# MCU.net
KiCad netlist of a schematic drawn in Altium Designer
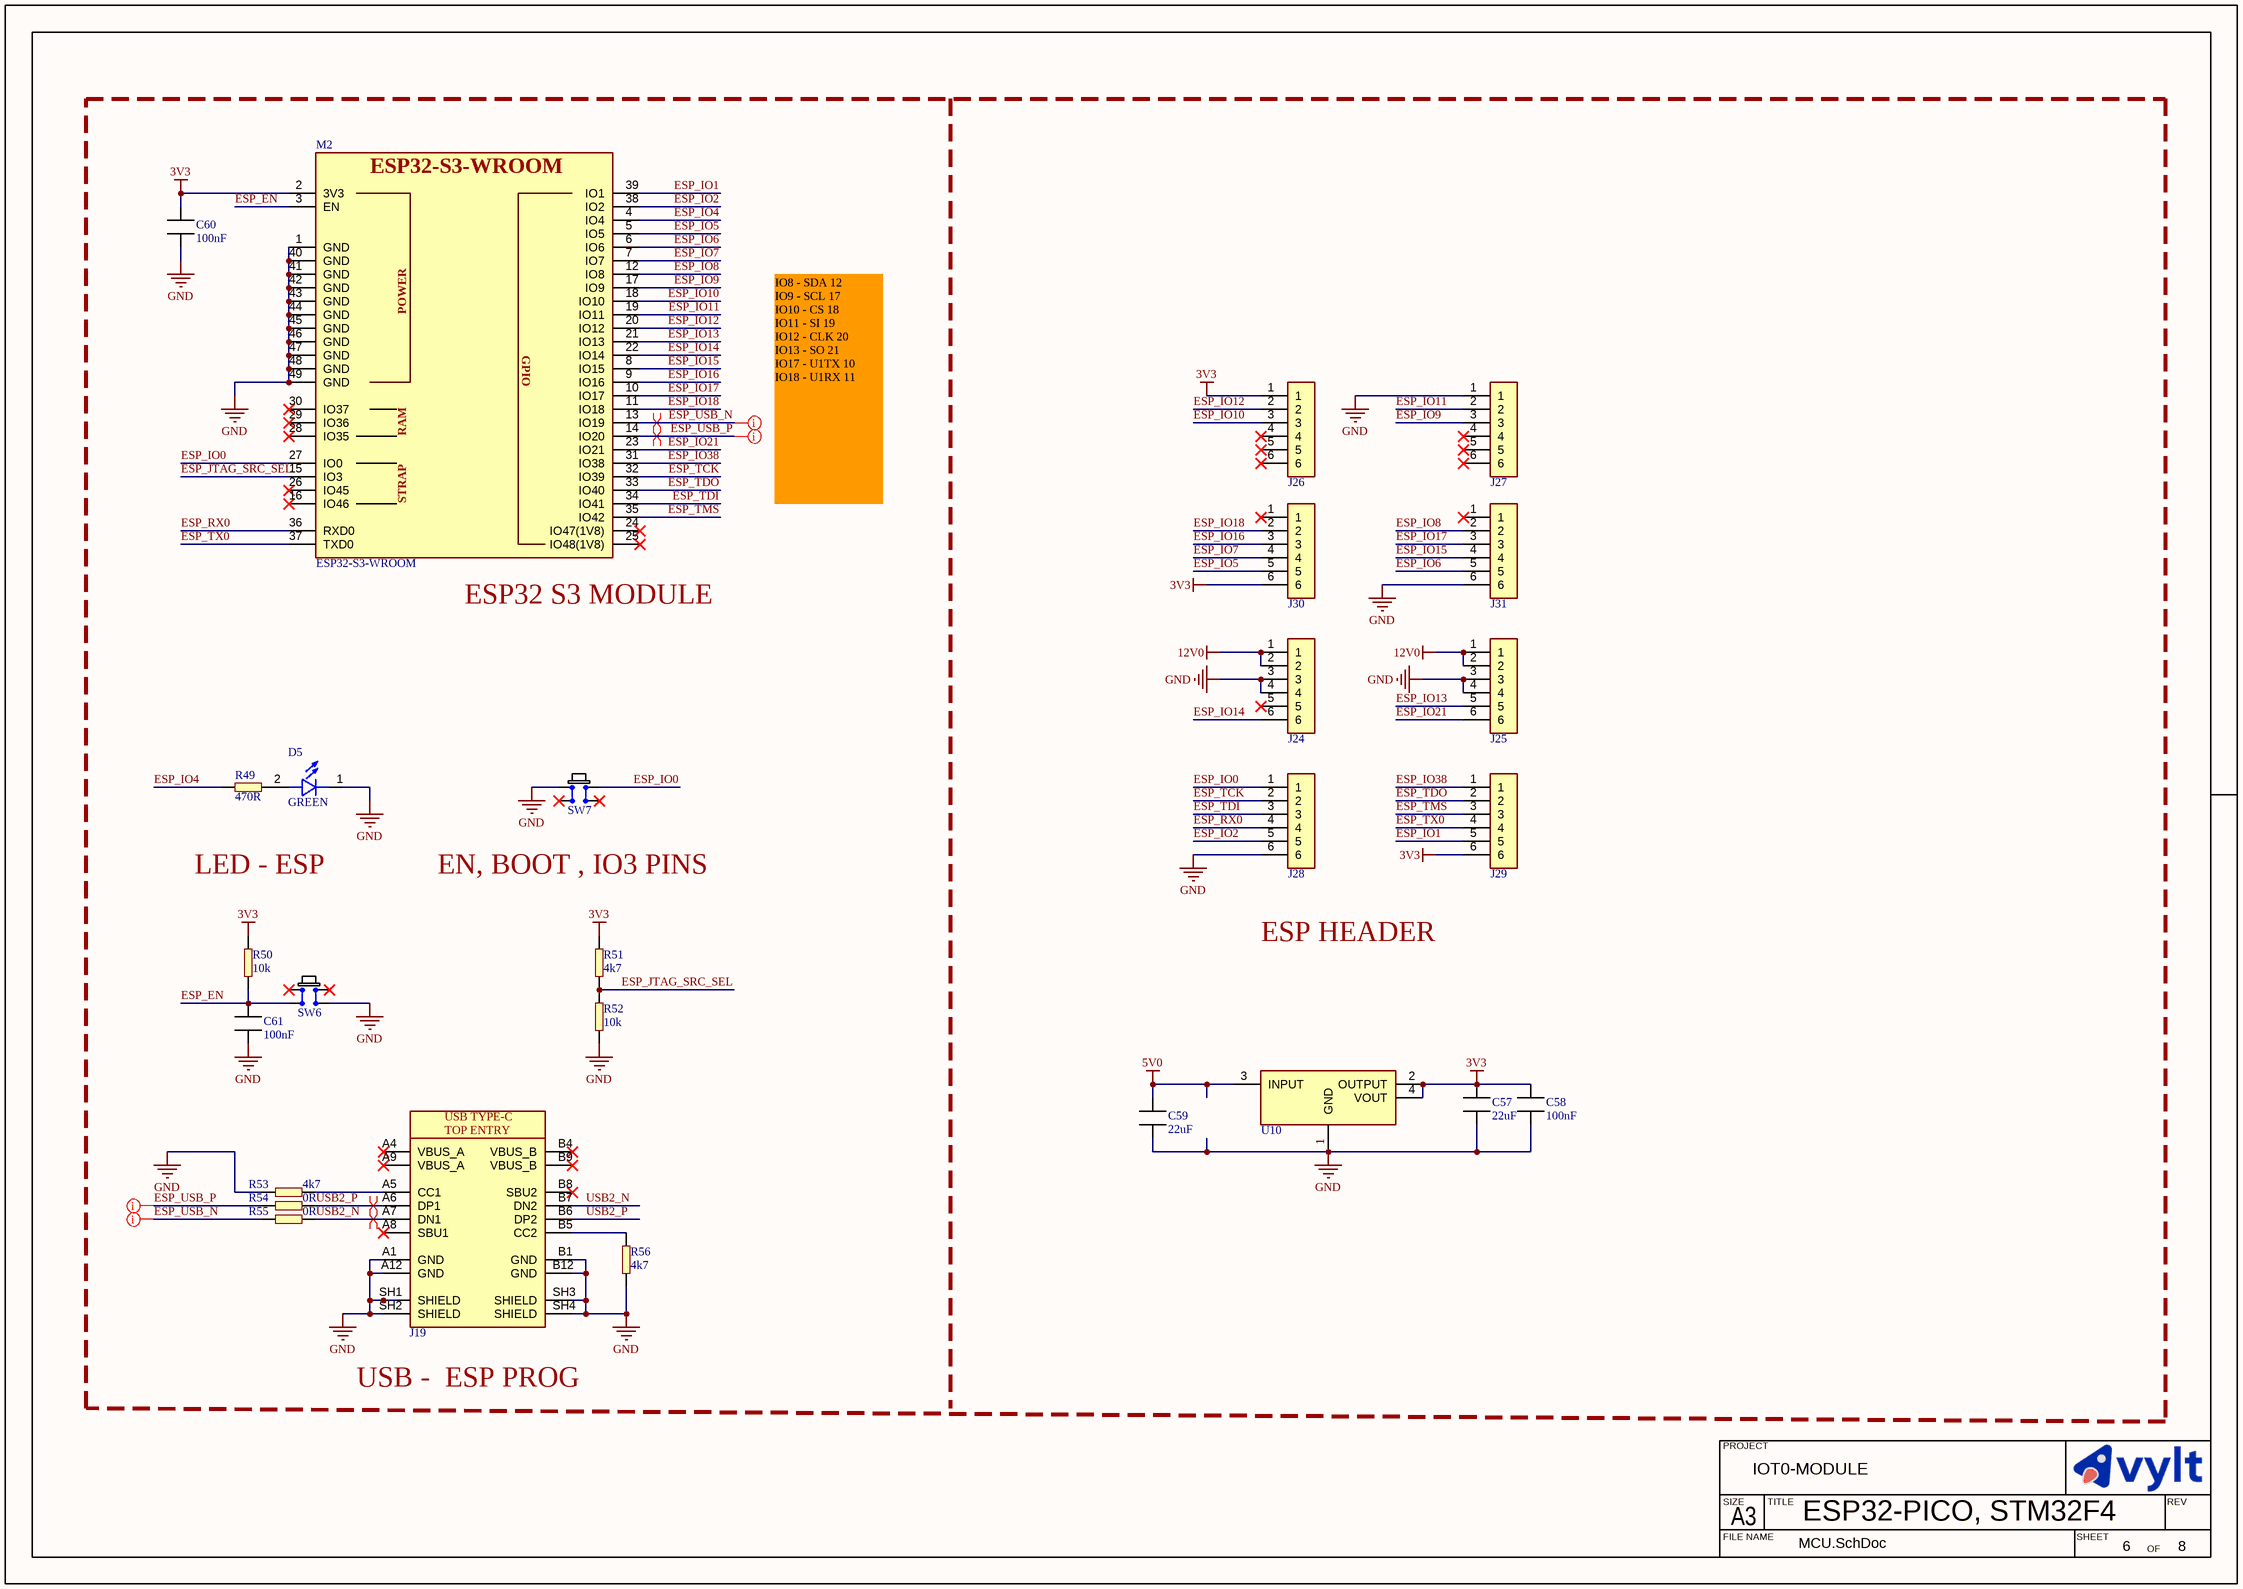
[diagram p0: MCU.SchDoc]

(export (version "E")
  (design (tool "Eeschema 10.0.6"))
  (components
    (comp (ref "C57")
      (value "22uF")
      (footprint "CAPC2012X13L")
      (description "Chip Capacitor, 2-Leads, Body 2.00x1.25mm, IPC High Density")
      (fields (field (name "Comment") "MLCC_0805"))
      (libsource (lib "Capacitor") (part "MLCC_0805"))
    )
    (comp (ref "C58")
      (value "100nF")
      (footprint "CAPC2012X13L")
      (description "Chip Capacitor, 2-Leads, Body 2.00x1.25mm, IPC High Density")
      (fields (field (name "Comment") "MLCC_0805"))
      (libsource (lib "Capacitor") (part "MLCC_0805"))
    )
    (comp (ref "C59")
      (value "22uF")
      (footprint "CAPC2012X13L")
      (description "Chip Capacitor, 2-Leads, Body 2.00x1.25mm, IPC High Density")
      (fields (field (name "Comment") "MLCC_0805"))
      (libsource (lib "Capacitor") (part "MLCC_0805"))
    )
    (comp (ref "C60")
      (value "100nF")
      (footprint "CAPC2012X13L")
      (description "Chip Capacitor, 2-Leads, Body 2.00x1.25mm, IPC High Density")
      (fields (field (name "Comment") "MLCC_0805"))
      (libsource (lib "Capacitor") (part "MLCC_0805"))
    )
    (comp (ref "C61")
      (value "100nF")
      (footprint "CAPC2012X13L")
      (description "Chip Capacitor, 2-Leads, Body 2.00x1.25mm, IPC High Density")
      (fields (field (name "Comment") "MLCC_0805"))
      (libsource (lib "Capacitor") (part "MLCC_0805"))
    )
    (comp (ref "D5")
      (value "GREEN")
      (footprint "LED_1206")
      (description "LED CLEAR 1206 SMD")
      (fields (field (name "Comment") "LED_1206"))
      (libsource (lib "LED") (part "LED_1206"))
    )
    (comp (ref "J19")
      (value "GSB1CA11101DSHR")
      (footprint "GSB1CA11101DSHR")
      (libsource (lib "Connectors") (part "GSB1CA11101DSHR"))
    )
    (comp (ref "J24")
      (value "ERP_148-2")
      (footprint "6PX1R_F")
      (description "6PX1R Female Header")
      (libsource (lib "PinHeader") (part "6PX1R_F"))
    )
    (comp (ref "J25")
      (value "ERP_148-2")
      (footprint "6PX1R_F")
      (description "6PX1R Female Header")
      (libsource (lib "PinHeader") (part "6PX1R_F"))
    )
    (comp (ref "J26")
      (value "ERP_148-2")
      (footprint "6PX1R_F")
      (description "6PX1R Female Header")
      (libsource (lib "PinHeader") (part "6PX1R_F"))
    )
    (comp (ref "J27")
      (value "ERP_148-2")
      (footprint "6PX1R_F")
      (description "6PX1R Female Header")
      (libsource (lib "PinHeader") (part "6PX1R_F"))
    )
    (comp (ref "J28")
      (value "ERP_148-2")
      (footprint "6PX1R_F")
      (description "6PX1R Female Header")
      (libsource (lib "PinHeader") (part "6PX1R_F"))
    )
    (comp (ref "J29")
      (value "ERP_148-2")
      (footprint "6PX1R_F")
      (description "6PX1R Female Header")
      (libsource (lib "PinHeader") (part "6PX1R_F"))
    )
    (comp (ref "J30")
      (value "ERP_148-2")
      (footprint "6PX1R_F")
      (description "6PX1R Female Header")
      (libsource (lib "PinHeader") (part "6PX1R_F"))
    )
    (comp (ref "J31")
      (value "ERP_148-2")
      (footprint "6PX1R_F")
      (description "6PX1R Female Header")
      (libsource (lib "PinHeader") (part "6PX1R_F"))
    )
    (comp (ref "M2")
      (value "ESP32-S3-WROOM")
      (footprint "ESP32-S3-WROOM-1")
      (description "ESP32-S3-WROOM 1/1U Module")
      (fields (field (name "Comment") "ESP32-S3-WROOM-1(U)"))
      (libsource (lib "ESP") (part "ESP32-S3-WROOM-1(U)"))
    )
    (comp (ref "R49")
      (value "470R")
      (footprint "RES_0603")
      (description "RES_0603")
      (fields (field (name "Comment") "ERP_101-1"))
      (libsource (lib "Resistor") (part "RES_0603"))
    )
    (comp (ref "R50")
      (value "10k")
      (footprint "RES_0603")
      (description "RES_0603")
      (fields (field (name "Comment") "ERP_101-1"))
      (libsource (lib "") (part "RES_0603_1"))
    )
    (comp (ref "R51")
      (value "4k7")
      (footprint "RES_0603")
      (description "RES_0603")
      (fields (field (name "Comment") "ERP_101-1"))
      (libsource (lib "") (part "RES_0603_1"))
    )
    (comp (ref "R52")
      (value "10k")
      (footprint "RES_0603")
      (description "RES_0603")
      (fields (field (name "Comment") "ERP_101-1"))
      (libsource (lib "") (part "RES_0603_1"))
    )
    (comp (ref "R53")
      (value "4k7")
      (footprint "RES_0603")
      (description "RES_0603")
      (fields (field (name "Comment") "ERP_101-1"))
      (libsource (lib "Resistor") (part "RES_0603"))
    )
    (comp (ref "R54")
      (value "0R")
      (footprint "RES_0603")
      (description "RES_0603")
      (fields (field (name "Comment") "ERP_101-1"))
      (libsource (lib "Resistor") (part "RES_0603"))
    )
    (comp (ref "R55")
      (value "0R")
      (footprint "RES_0603")
      (description "RES_0603")
      (fields (field (name "Comment") "ERP_101-1"))
      (libsource (lib "Resistor") (part "RES_0603"))
    )
    (comp (ref "R56")
      (value "4k7")
      (footprint "RES_0603")
      (description "RES_0603")
      (fields (field (name "Comment") "ERP_101-1"))
      (libsource (lib "") (part "RES_0603_2"))
    )
    (comp (ref "SW6")
      (value "Generic6X6")
      (footprint "Generic6X6")
      (description "Tactile Switch SPST-NO Top Actuated Surface Mount")
      (libsource (lib "Switch") (part "Generic6X6"))
    )
    (comp (ref "SW7")
      (value "Generic6X6")
      (footprint "Generic6X6")
      (description "Tactile Switch SPST-NO Top Actuated Surface Mount")
      (libsource (lib "Switch") (part "Generic6X6"))
    )
    (comp (ref "U10")
      (value "ERP_123-1")
      (footprint "AMS1117_SOT223")
      (description "AMS1117 LDO")
      (libsource (lib "VoltageRegulator") (part "AMS1117_SOT223"))
    )
  )
  (nets
    (net (code "1") (name "/ESP_EN") (class "Default")
      (node (ref "C61") (pin "1") (pinfunction "1_1") (pintype "passive"))
      (node (ref "M2") (pin "3") (pinfunction "EN_3") (pintype "passive"))
      (node (ref "R50") (pin "1") (pinfunction "1_1") (pintype "passive"))
      (node (ref "SW6") (pin "2") (pinfunction "NO_2") (pintype "passive"))
    )
    (net (code "2") (name "/ESP_IO0") (class "Default")
      (node (ref "J28") (pin "1") (pinfunction "1_1") (pintype "passive"))
      (node (ref "M2") (pin "27") (pinfunction "IO0_27") (pintype "passive"))
      (node (ref "SW7") (pin "3") (pinfunction "COM_3") (pintype "passive"))
    )
    (net (code "3") (name "/ESP_IO1") (class "Default")
      (node (ref "J29") (pin "5") (pinfunction "5_5") (pintype "passive"))
      (node (ref "M2") (pin "39") (pinfunction "IO1_39") (pintype "passive"))
    )
    (net (code "4") (name "/ESP_IO2") (class "Default")
      (node (ref "J28") (pin "5") (pinfunction "5_5") (pintype "passive"))
      (node (ref "M2") (pin "38") (pinfunction "IO2_38") (pintype "passive"))
    )
    (net (code "5") (name "/ESP_IO4") (class "Default")
      (node (ref "M2") (pin "4") (pinfunction "IO4_4") (pintype "passive"))
      (node (ref "R49") (pin "2") (pinfunction "2_2") (pintype "passive"))
    )
    (net (code "6") (name "/ESP_IO5") (class "Default")
      (node (ref "J30") (pin "5") (pinfunction "5_5") (pintype "passive"))
      (node (ref "M2") (pin "5") (pinfunction "IO5_5") (pintype "passive"))
    )
    (net (code "7") (name "/ESP_IO6") (class "Default")
      (node (ref "J31") (pin "5") (pinfunction "5_5") (pintype "passive"))
      (node (ref "M2") (pin "6") (pinfunction "IO6_6") (pintype "passive"))
    )
    (net (code "8") (name "/ESP_IO7") (class "Default")
      (node (ref "J30") (pin "4") (pinfunction "4_4") (pintype "passive"))
      (node (ref "M2") (pin "7") (pinfunction "IO7_7") (pintype "passive"))
    )
    (net (code "9") (name "/ESP_IO8") (class "Default")
      (node (ref "J31") (pin "2") (pinfunction "2_2") (pintype "passive"))
      (node (ref "M2") (pin "12") (pinfunction "IO8_12") (pintype "passive"))
    )
    (net (code "10") (name "/ESP_IO9") (class "Default")
      (node (ref "J27") (pin "3") (pinfunction "3_3") (pintype "passive"))
      (node (ref "M2") (pin "17") (pinfunction "IO9_17") (pintype "passive"))
    )
    (net (code "11") (name "/ESP_IO10") (class "Default")
      (node (ref "J26") (pin "3") (pinfunction "3_3") (pintype "passive"))
      (node (ref "M2") (pin "18") (pinfunction "IO10_18") (pintype "passive"))
    )
    (net (code "12") (name "/ESP_IO11") (class "Default")
      (node (ref "J27") (pin "2") (pinfunction "2_2") (pintype "passive"))
      (node (ref "M2") (pin "19") (pinfunction "IO11_19") (pintype "passive"))
    )
    (net (code "13") (name "/ESP_IO12") (class "Default")
      (node (ref "J26") (pin "2") (pinfunction "2_2") (pintype "passive"))
      (node (ref "M2") (pin "20") (pinfunction "IO12_20") (pintype "passive"))
    )
    (net (code "14") (name "/ESP_IO13") (class "Default")
      (node (ref "J25") (pin "5") (pinfunction "5_5") (pintype "passive"))
      (node (ref "M2") (pin "21") (pinfunction "IO13_21") (pintype "passive"))
    )
    (net (code "15") (name "/ESP_IO14") (class "Default")
      (node (ref "J24") (pin "6") (pinfunction "6_6") (pintype "passive"))
      (node (ref "M2") (pin "22") (pinfunction "IO14_22") (pintype "passive"))
    )
    (net (code "16") (name "/ESP_IO15") (class "Default")
      (node (ref "J31") (pin "4") (pinfunction "4_4") (pintype "passive"))
      (node (ref "M2") (pin "8") (pinfunction "IO15_8") (pintype "passive"))
    )
    (net (code "17") (name "/ESP_IO16") (class "Default")
      (node (ref "J30") (pin "3") (pinfunction "3_3") (pintype "passive"))
      (node (ref "M2") (pin "9") (pinfunction "IO16_9") (pintype "passive"))
    )
    (net (code "18") (name "/ESP_IO17") (class "Default")
      (node (ref "J31") (pin "3") (pinfunction "3_3") (pintype "passive"))
      (node (ref "M2") (pin "10") (pinfunction "IO17_10") (pintype "passive"))
    )
    (net (code "19") (name "/ESP_IO18") (class "Default")
      (node (ref "J30") (pin "2") (pinfunction "2_2") (pintype "passive"))
      (node (ref "M2") (pin "11") (pinfunction "IO18_11") (pintype "passive"))
    )
    (net (code "20") (name "/ESP_IO21") (class "Default")
      (node (ref "J25") (pin "6") (pinfunction "6_6") (pintype "passive"))
      (node (ref "M2") (pin "23") (pinfunction "IO21_23") (pintype "passive"))
    )
    (net (code "21") (name "/ESP_IO38") (class "Default")
      (node (ref "J29") (pin "1") (pinfunction "1_1") (pintype "passive"))
      (node (ref "M2") (pin "31") (pinfunction "IO38_31") (pintype "passive"))
    )
    (net (code "22") (name "/ESP_JTAG_SRC_SEL") (class "Default")
      (node (ref "M2") (pin "15") (pinfunction "IO3_15") (pintype "passive"))
      (node (ref "R51") (pin "1") (pinfunction "1_1") (pintype "passive"))
      (node (ref "R52") (pin "2") (pinfunction "2_2") (pintype "passive"))
    )
    (net (code "23") (name "/ESP_RX0") (class "Default")
      (node (ref "J28") (pin "4") (pinfunction "4_4") (pintype "passive"))
      (node (ref "M2") (pin "36") (pinfunction "RXD0_36") (pintype "passive"))
    )
    (net (code "24") (name "/ESP_TCK") (class "Default")
      (node (ref "J28") (pin "2") (pinfunction "2_2") (pintype "passive"))
      (node (ref "M2") (pin "32") (pinfunction "IO39_32") (pintype "passive"))
    )
    (net (code "25") (name "/ESP_TDI") (class "Default")
      (node (ref "J28") (pin "3") (pinfunction "3_3") (pintype "passive"))
      (node (ref "M2") (pin "34") (pinfunction "IO41_34") (pintype "passive"))
    )
    (net (code "26") (name "/ESP_TDO") (class "Default")
      (node (ref "J29") (pin "2") (pinfunction "2_2") (pintype "passive"))
      (node (ref "M2") (pin "33") (pinfunction "IO40_33") (pintype "passive"))
    )
    (net (code "27") (name "/ESP_TMS") (class "Default")
      (node (ref "J29") (pin "3") (pinfunction "3_3") (pintype "passive"))
      (node (ref "M2") (pin "35") (pinfunction "IO42_35") (pintype "passive"))
    )
    (net (code "28") (name "/ESP_TX0") (class "Default")
      (node (ref "J29") (pin "4") (pinfunction "4_4") (pintype "passive"))
      (node (ref "M2") (pin "37") (pinfunction "TXD0_37") (pintype "passive"))
    )
    (net (code "29") (name "/ESP_USB_N") (class "Default")
      (node (ref "M2") (pin "13") (pinfunction "IO19_13") (pintype "passive"))
      (node (ref "R55") (pin "2") (pinfunction "2_2") (pintype "passive"))
    )
    (net (code "30") (name "/ESP_USB_P") (class "Default")
      (node (ref "M2") (pin "14") (pinfunction "IO20_14") (pintype "passive"))
      (node (ref "R54") (pin "2") (pinfunction "2_2") (pintype "passive"))
    )
    (net (code "31") (name "/USB2_N") (class "Default")
      (node (ref "J19") (pin "A7") (pinfunction "DN1_A7") (pintype "passive"))
      (node (ref "J19") (pin "B7") (pinfunction "DN2_B7") (pintype "passive"))
      (node (ref "R55") (pin "1") (pinfunction "1_1") (pintype "passive"))
    )
    (net (code "32") (name "/USB2_P") (class "Default")
      (node (ref "J19") (pin "A6") (pinfunction "DP1_A6") (pintype "passive"))
      (node (ref "J19") (pin "B6") (pinfunction "DP2_B6") (pintype "passive"))
      (node (ref "R54") (pin "1") (pinfunction "1_1") (pintype "passive"))
    )
    (net (code "33") (name "3V3") (class "Default")
      (node (ref "C57") (pin "1") (pinfunction "1_1") (pintype "passive"))
      (node (ref "C58") (pin "1") (pinfunction "1_1") (pintype "passive"))
      (node (ref "C60") (pin "1") (pinfunction "1_1") (pintype "passive"))
      (node (ref "J26") (pin "1") (pinfunction "1_1") (pintype "passive"))
      (node (ref "J29") (pin "6") (pinfunction "6_6") (pintype "passive"))
      (node (ref "J30") (pin "6") (pinfunction "6_6") (pintype "passive"))
      (node (ref "M2") (pin "2") (pinfunction "3V3_2") (pintype "passive"))
      (node (ref "R50") (pin "2") (pinfunction "2_2") (pintype "passive"))
      (node (ref "R51") (pin "2") (pinfunction "2_2") (pintype "passive"))
      (node (ref "U10") (pin "2") (pinfunction "OUTPUT_2") (pintype "passive"))
      (node (ref "U10") (pin "4") (pinfunction "VOUT_4") (pintype "passive"))
    )
    (net (code "34") (name "5V0") (class "Default")
      (node (ref "C59") (pin "1") (pinfunction "1_1") (pintype "passive"))
      (node (ref "U10") (pin "3") (pinfunction "INPUT_3") (pintype "passive"))
    )
    (net (code "35") (name "12V0") (class "Default")
      (node (ref "J24") (pin "1") (pinfunction "1_1") (pintype "passive"))
      (node (ref "J24") (pin "2") (pinfunction "2_2") (pintype "passive"))
      (node (ref "J25") (pin "1") (pinfunction "1_1") (pintype "passive"))
      (node (ref "J25") (pin "2") (pinfunction "2_2") (pintype "passive"))
    )
    (net (code "36") (name "GND") (class "Default")
      (node (ref "C57") (pin "2") (pinfunction "2_2") (pintype "passive"))
      (node (ref "C58") (pin "2") (pinfunction "2_2") (pintype "passive"))
      (node (ref "C59") (pin "2") (pinfunction "2_2") (pintype "passive"))
      (node (ref "C60") (pin "2") (pinfunction "2_2") (pintype "passive"))
      (node (ref "C61") (pin "2") (pinfunction "2_2") (pintype "passive"))
      (node (ref "D5") (pin "1") (pinfunction "1_1") (pintype "passive"))
      (node (ref "J19") (pin "A1") (pinfunction "GND_A1") (pintype "power_in"))
      (node (ref "J19") (pin "A12") (pinfunction "GND_A12") (pintype "power_in"))
      (node (ref "J19") (pin "B1") (pinfunction "GND_B1") (pintype "power_in"))
      (node (ref "J19") (pin "B12") (pinfunction "GND_B12") (pintype "power_in"))
      (node (ref "J19") (pin "SH1") (pinfunction "SHIELD_SH1") (pintype "passive"))
      (node (ref "J19") (pin "SH2") (pinfunction "SHIELD_SH2") (pintype "passive"))
      (node (ref "J19") (pin "SH3") (pinfunction "SHIELD_SH3") (pintype "passive"))
      (node (ref "J19") (pin "SH4") (pinfunction "SHIELD_SH4") (pintype "passive"))
      (node (ref "J24") (pin "3") (pinfunction "3_3") (pintype "passive"))
      (node (ref "J24") (pin "4") (pinfunction "4_4") (pintype "passive"))
      (node (ref "J25") (pin "3") (pinfunction "3_3") (pintype "passive"))
      (node (ref "J25") (pin "4") (pinfunction "4_4") (pintype "passive"))
      (node (ref "J27") (pin "1") (pinfunction "1_1") (pintype "passive"))
      (node (ref "J28") (pin "6") (pinfunction "6_6") (pintype "passive"))
      (node (ref "J31") (pin "6") (pinfunction "6_6") (pintype "passive"))
      (node (ref "M2") (pin "1") (pinfunction "GND_1") (pintype "power_in"))
      (node (ref "M2") (pin "40") (pinfunction "GND_40") (pintype "power_in"))
      (node (ref "M2") (pin "41") (pinfunction "GND_41") (pintype "power_in"))
      (node (ref "M2") (pin "42") (pinfunction "GND_42") (pintype "power_in"))
      (node (ref "M2") (pin "43") (pinfunction "GND_43") (pintype "power_in"))
      (node (ref "M2") (pin "44") (pinfunction "GND_44") (pintype "power_in"))
      (node (ref "M2") (pin "45") (pinfunction "GND_45") (pintype "power_in"))
      (node (ref "M2") (pin "46") (pinfunction "GND_46") (pintype "power_in"))
      (node (ref "M2") (pin "47") (pinfunction "GND_47") (pintype "power_in"))
      (node (ref "M2") (pin "48") (pinfunction "GND_48") (pintype "power_in"))
      (node (ref "M2") (pin "49") (pinfunction "GND_49") (pintype "power_in"))
      (node (ref "R52") (pin "1") (pinfunction "1_1") (pintype "passive"))
      (node (ref "R53") (pin "2") (pinfunction "2_2") (pintype "passive"))
      (node (ref "R56") (pin "2") (pinfunction "2_2") (pintype "passive"))
      (node (ref "SW6") (pin "4") (pinfunction "COM_4") (pintype "passive"))
      (node (ref "SW7") (pin "1") (pinfunction "NO_1") (pintype "passive"))
      (node (ref "U10") (pin "1") (pinfunction "GND_1") (pintype "power_in"))
    )
    (net (code "37") (name "Net-(D5-Pad2)") (class "Default")
      (node (ref "D5") (pin "2") (pinfunction "2_2") (pintype "passive"))
      (node (ref "R49") (pin "1") (pinfunction "1_1") (pintype "passive"))
    )
    (net (code "38") (name "Net-(J19-CC1)") (class "Default")
      (node (ref "J19") (pin "A5") (pinfunction "CC1_A5") (pintype "passive"))
      (node (ref "R53") (pin "1") (pinfunction "1_1") (pintype "passive"))
    )
    (net (code "39") (name "Net-(J19-CC2)") (class "Default")
      (node (ref "J19") (pin "B5") (pinfunction "CC2_B5") (pintype "passive"))
      (node (ref "R56") (pin "1") (pinfunction "1_1") (pintype "passive"))
    )
    (net (code "40") (name "unconnected-(J19-SBU1-PadA8)") (class "Default")
      (node (ref "J19") (pin "A8") (pinfunction "SBU1_A8") (pintype "passive+no_connect"))
    )
    (net (code "41") (name "unconnected-(J19-SBU2-PadB8)") (class "Default")
      (node (ref "J19") (pin "B8") (pinfunction "SBU2_B8") (pintype "passive+no_connect"))
    )
    (net (code "42") (name "unconnected-(J19-VBUS_A-PadA4)") (class "Default")
      (node (ref "J19") (pin "A4") (pinfunction "VBUS_A_A4") (pintype "power_in+no_connect"))
    )
    (net (code "43") (name "unconnected-(J19-VBUS_A-PadA9)") (class "Default")
      (node (ref "J19") (pin "A9") (pinfunction "VBUS_A_A9") (pintype "power_in+no_connect"))
    )
    (net (code "44") (name "unconnected-(J19-VBUS_B-PadB4)") (class "Default")
      (node (ref "J19") (pin "B4") (pinfunction "VBUS_B_B4") (pintype "power_in+no_connect"))
    )
    (net (code "45") (name "unconnected-(J19-VBUS_B-PadB9)") (class "Default")
      (node (ref "J19") (pin "B9") (pinfunction "VBUS_B_B9") (pintype "power_in+no_connect"))
    )
    (net (code "46") (name "unconnected-(J24-Pad5)") (class "Default")
      (node (ref "J24") (pin "5") (pinfunction "5_5") (pintype "passive+no_connect"))
    )
    (net (code "47") (name "unconnected-(J26-Pad4)") (class "Default")
      (node (ref "J26") (pin "4") (pinfunction "4_4") (pintype "passive+no_connect"))
    )
    (net (code "48") (name "unconnected-(J26-Pad5)") (class "Default")
      (node (ref "J26") (pin "5") (pinfunction "5_5") (pintype "passive+no_connect"))
    )
    (net (code "49") (name "unconnected-(J26-Pad6)") (class "Default")
      (node (ref "J26") (pin "6") (pinfunction "6_6") (pintype "passive+no_connect"))
    )
    (net (code "50") (name "unconnected-(J27-Pad4)") (class "Default")
      (node (ref "J27") (pin "4") (pinfunction "4_4") (pintype "passive+no_connect"))
    )
    (net (code "51") (name "unconnected-(J27-Pad5)") (class "Default")
      (node (ref "J27") (pin "5") (pinfunction "5_5") (pintype "passive+no_connect"))
    )
    (net (code "52") (name "unconnected-(J27-Pad6)") (class "Default")
      (node (ref "J27") (pin "6") (pinfunction "6_6") (pintype "passive+no_connect"))
    )
    (net (code "53") (name "unconnected-(J30-Pad1)") (class "Default")
      (node (ref "J30") (pin "1") (pinfunction "1_1") (pintype "passive+no_connect"))
    )
    (net (code "54") (name "unconnected-(J31-Pad1)") (class "Default")
      (node (ref "J31") (pin "1") (pinfunction "1_1") (pintype "passive+no_connect"))
    )
    (net (code "55") (name "unconnected-(M2-IO35-Pad28)") (class "Default")
      (node (ref "M2") (pin "28") (pinfunction "IO35_28") (pintype "passive+no_connect"))
    )
    (net (code "56") (name "unconnected-(M2-IO36-Pad29)") (class "Default")
      (node (ref "M2") (pin "29") (pinfunction "IO36_29") (pintype "passive+no_connect"))
    )
    (net (code "57") (name "unconnected-(M2-IO37-Pad30)") (class "Default")
      (node (ref "M2") (pin "30") (pinfunction "IO37_30") (pintype "passive+no_connect"))
    )
    (net (code "58") (name "unconnected-(M2-IO45-Pad26)") (class "Default")
      (node (ref "M2") (pin "26") (pinfunction "IO45_26") (pintype "passive+no_connect"))
    )
    (net (code "59") (name "unconnected-(M2-IO46-Pad16)") (class "Default")
      (node (ref "M2") (pin "16") (pinfunction "IO46_16") (pintype "passive+no_connect"))
    )
    (net (code "60") (name "unconnected-(M2-IO47(1V8)-Pad24)") (class "Default")
      (node (ref "M2") (pin "24") (pinfunction "IO47(1V8)_24") (pintype "passive+no_connect"))
    )
    (net (code "61") (name "unconnected-(M2-IO48(1V8)-Pad25)") (class "Default")
      (node (ref "M2") (pin "25") (pinfunction "IO48(1V8)_25") (pintype "passive+no_connect"))
    )
    (net (code "62") (name "unconnected-(SW6-COM-Pad3)") (class "Default")
      (node (ref "SW6") (pin "3") (pinfunction "COM_3") (pintype "passive+no_connect"))
    )
    (net (code "63") (name "unconnected-(SW6-NO-Pad1)") (class "Default")
      (node (ref "SW6") (pin "1") (pinfunction "NO_1") (pintype "passive+no_connect"))
    )
    (net (code "64") (name "unconnected-(SW7-COM-Pad4)") (class "Default")
      (node (ref "SW7") (pin "4") (pinfunction "COM_4") (pintype "passive+no_connect"))
    )
    (net (code "65") (name "unconnected-(SW7-NO-Pad2)") (class "Default")
      (node (ref "SW7") (pin "2") (pinfunction "NO_2") (pintype "passive+no_connect"))
    )
  )
)
